# MD.net
KiCad netlist of a schematic drawn in EAGLE
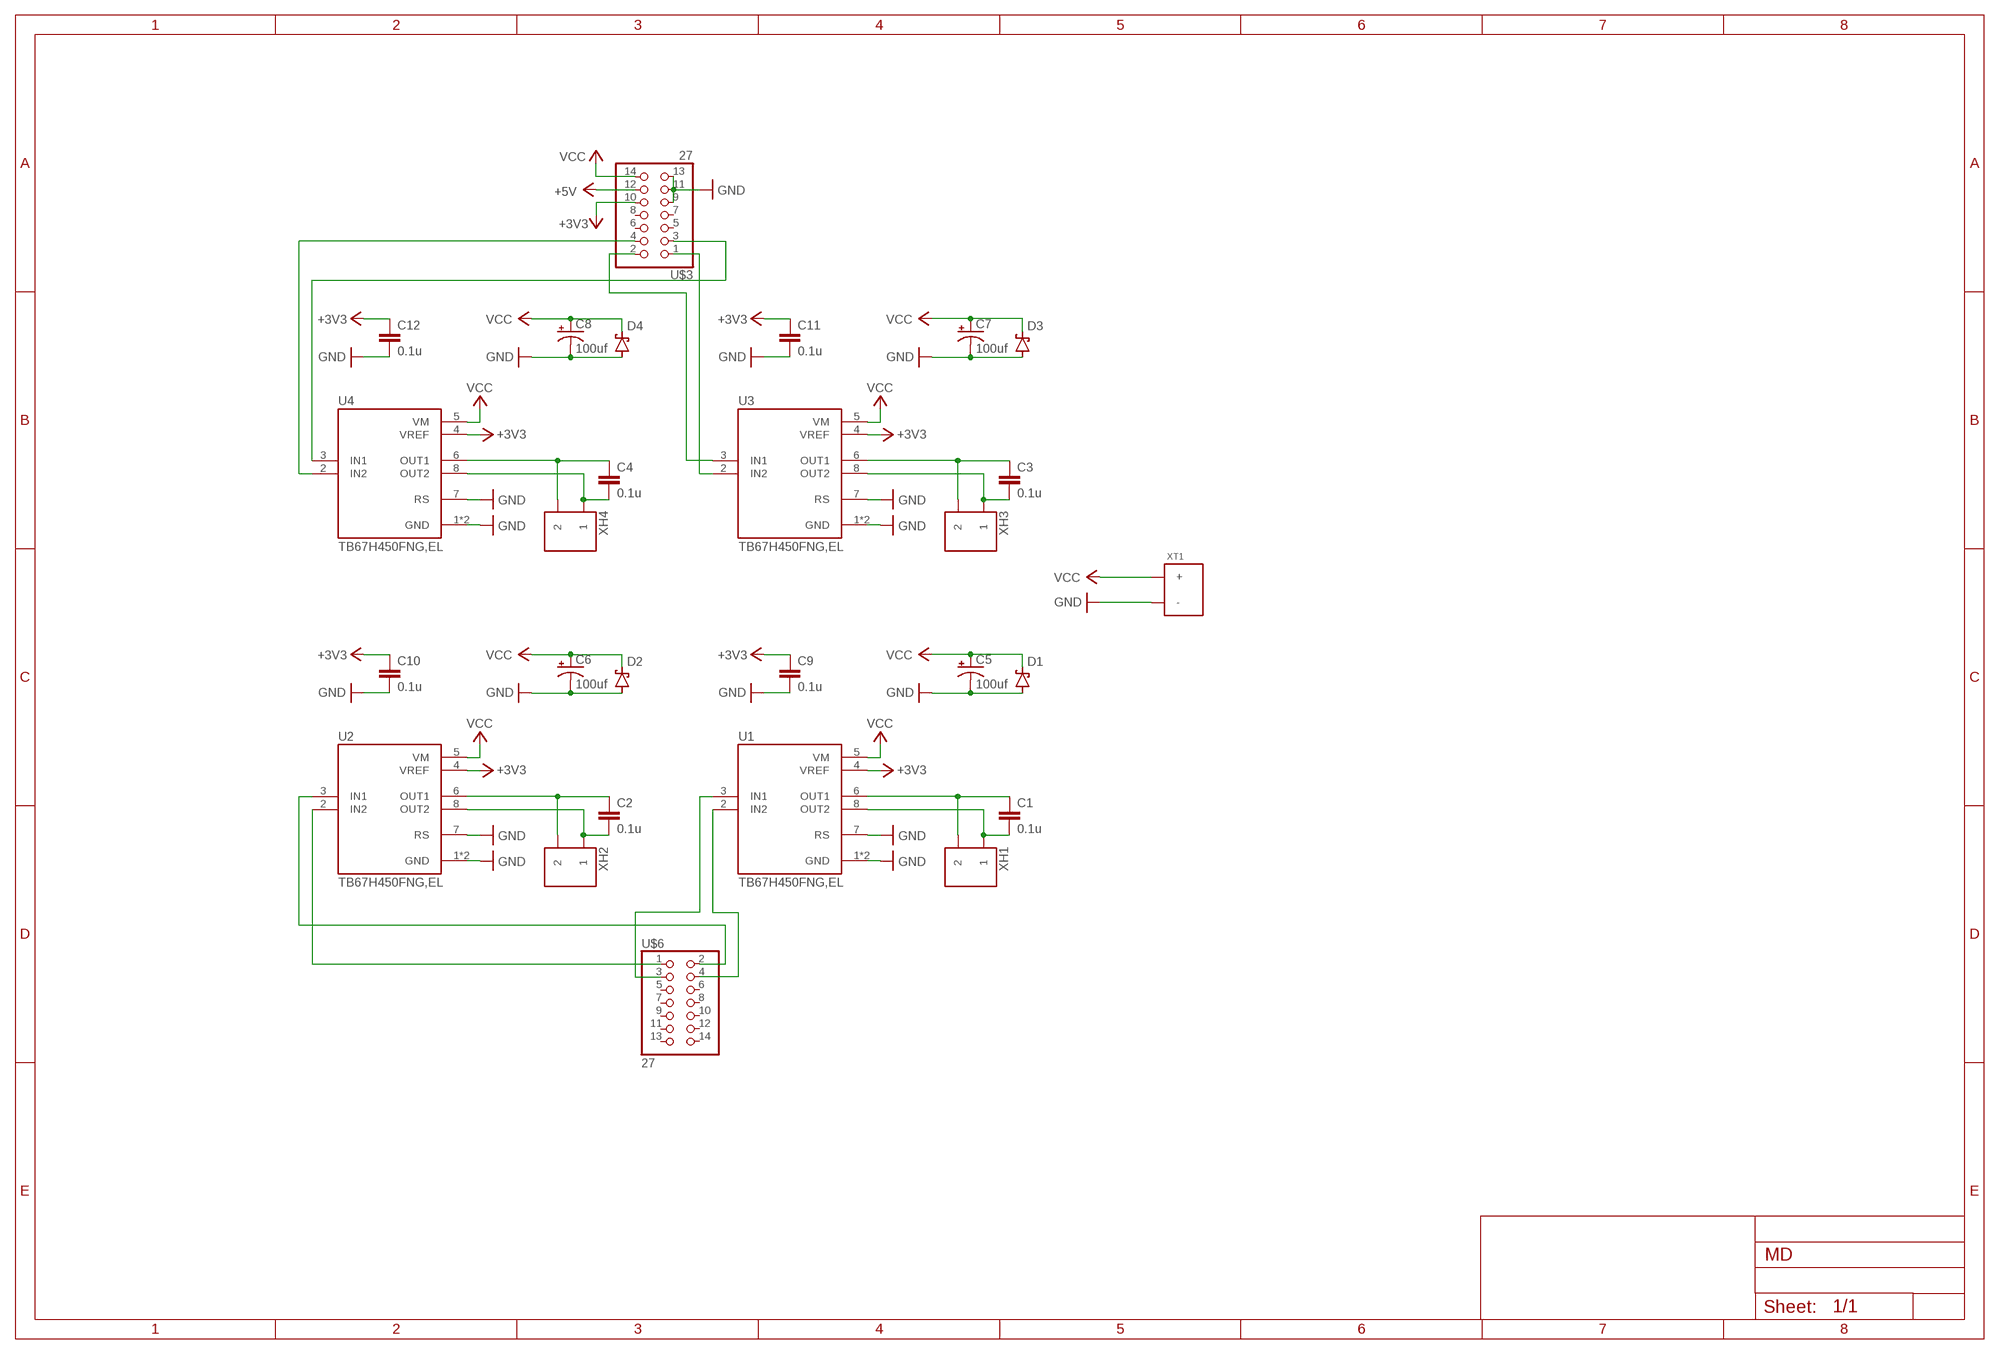
[diagram p0: schematic, sheet 1]

(export (version "E")
  (design (tool "Eeschema 10.0.6"))
  (components
    (comp (ref "C1")
      (value "0.1u")
      (footprint "eagle-import:C0603")
      (libsource (lib "eagle-import") (part "C-EUC0603"))
    )
    (comp (ref "C2")
      (value "0.1u")
      (footprint "eagle-import:C0603")
      (libsource (lib "eagle-import") (part "C-EUC0603"))
    )
    (comp (ref "C3")
      (value "0.1u")
      (footprint "eagle-import:C0603")
      (libsource (lib "eagle-import") (part "C-EUC0603"))
    )
    (comp (ref "C4")
      (value "0.1u")
      (footprint "eagle-import:C0603")
      (libsource (lib "eagle-import") (part "C-EUC0603"))
    )
    (comp (ref "C5")
      (value "100uf")
      (footprint "eagle-import:MH5")
      (libsource (lib "eagle-import") (part "MH5"))
    )
    (comp (ref "C6")
      (value "100uf")
      (footprint "eagle-import:MH5")
      (libsource (lib "eagle-import") (part "MH5"))
    )
    (comp (ref "C7")
      (value "100uf")
      (footprint "eagle-import:MH5")
      (libsource (lib "eagle-import") (part "MH5"))
    )
    (comp (ref "C8")
      (value "100uf")
      (footprint "eagle-import:MH5")
      (libsource (lib "eagle-import") (part "MH5"))
    )
    (comp (ref "C9")
      (value "0.1u")
      (footprint "eagle-import:C0603")
      (libsource (lib "eagle-import") (part "C-EUC0603"))
    )
    (comp (ref "C10")
      (value "0.1u")
      (footprint "eagle-import:C0603")
      (libsource (lib "eagle-import") (part "C-EUC0603"))
    )
    (comp (ref "C11")
      (value "0.1u")
      (footprint "eagle-import:C0603")
      (libsource (lib "eagle-import") (part "C-EUC0603"))
    )
    (comp (ref "C12")
      (value "0.1u")
      (footprint "eagle-import:C0603")
      (libsource (lib "eagle-import") (part "C-EUC0603"))
    )
    (comp (ref "D1")
      (value "SS2040FL")
      (footprint "eagle-import:SOD123FL")
      (libsource (lib "eagle-import") (part "SS2040FL"))
    )
    (comp (ref "D2")
      (value "SS2040FL")
      (footprint "eagle-import:SOD123FL")
      (libsource (lib "eagle-import") (part "SS2040FL"))
    )
    (comp (ref "D3")
      (value "SS2040FL")
      (footprint "eagle-import:SOD123FL")
      (libsource (lib "eagle-import") (part "SS2040FL"))
    )
    (comp (ref "D4")
      (value "SS2040FL")
      (footprint "eagle-import:SOD123FL")
      (libsource (lib "eagle-import") (part "SS2040FL"))
    )
    (comp (ref "U$3")
      (value "27")
      (footprint "eagle-import:2_7")
      (libsource (lib "eagle-import") (part "27"))
    )
    (comp (ref "U$6")
      (value "27")
      (footprint "eagle-import:2_7")
      (libsource (lib "eagle-import") (part "27"))
    )
    (comp (ref "U1")
      (value "TB67H450FNG,EL")
      (footprint "eagle-import:SOIC127P599X175-9N")
      (fields (field (name "MF") "Toshiba Semiconductor and Storage"))
      (libsource (lib "eagle-import") (part "TB67H450FNG,EL"))
    )
    (comp (ref "U2")
      (value "TB67H450FNG,EL")
      (footprint "eagle-import:SOIC127P599X175-9N")
      (fields (field (name "MF") "Toshiba Semiconductor and Storage"))
      (libsource (lib "eagle-import") (part "TB67H450FNG,EL"))
    )
    (comp (ref "U3")
      (value "TB67H450FNG,EL")
      (footprint "eagle-import:SOIC127P599X175-9N")
      (fields (field (name "MF") "Toshiba Semiconductor and Storage"))
      (libsource (lib "eagle-import") (part "TB67H450FNG,EL"))
    )
    (comp (ref "U4")
      (value "TB67H450FNG,EL")
      (footprint "eagle-import:SOIC127P599X175-9N")
      (fields (field (name "MF") "Toshiba Semiconductor and Storage"))
      (libsource (lib "eagle-import") (part "TB67H450FNG,EL"))
    )
    (comp (ref "XH1")
      (value "S2B")
      (footprint "eagle-import:S2B")
      (libsource (lib "eagle-import") (part "S2B"))
    )
    (comp (ref "XH2")
      (value "S2B")
      (footprint "eagle-import:S2B")
      (libsource (lib "eagle-import") (part "S2B"))
    )
    (comp (ref "XH3")
      (value "S2B")
      (footprint "eagle-import:S2B")
      (libsource (lib "eagle-import") (part "S2B"))
    )
    (comp (ref "XH4")
      (value "S2B")
      (footprint "eagle-import:S2B")
      (libsource (lib "eagle-import") (part "S2B"))
    )
    (comp (ref "XT1")
      (value "XT30PW-M")
      (footprint "eagle-import:XT30PW-M")
      (libsource (lib "eagle-import") (part "XT30PW-M"))
    )
  )
  (nets
    (net (code "1") (name "+3V3") (class "Default")
      (node (ref "C10") (pin "1") (pinfunction "1_1") (pintype "passive"))
      (node (ref "C11") (pin "1") (pinfunction "1_1") (pintype "passive"))
      (node (ref "C12") (pin "1") (pinfunction "1_1") (pintype "passive"))
      (node (ref "C9") (pin "1") (pinfunction "1_1") (pintype "passive"))
      (node (ref "U$3") (pin "10") (pinfunction "10_10") (pintype "passive"))
      (node (ref "U1") (pin "4") (pinfunction "VREF_4") (pintype "power_in"))
      (node (ref "U2") (pin "4") (pinfunction "VREF_4") (pintype "power_in"))
      (node (ref "U3") (pin "4") (pinfunction "VREF_4") (pintype "power_in"))
      (node (ref "U4") (pin "4") (pinfunction "VREF_4") (pintype "power_in"))
    )
    (net (code "2") (name "+5V") (class "Default")
      (node (ref "U$3") (pin "12") (pinfunction "12_12") (pintype "passive"))
    )
    (net (code "3") (name "GND") (class "Default")
      (node (ref "C10") (pin "2") (pinfunction "2_2") (pintype "passive"))
      (node (ref "C11") (pin "2") (pinfunction "2_2") (pintype "passive"))
      (node (ref "C12") (pin "2") (pinfunction "2_2") (pintype "passive"))
      (node (ref "C5") (pin "-") (pinfunction "-_-") (pintype "passive"))
      (node (ref "C6") (pin "-") (pinfunction "-_-") (pintype "passive"))
      (node (ref "C7") (pin "-") (pinfunction "-_-") (pintype "passive"))
      (node (ref "C8") (pin "-") (pinfunction "-_-") (pintype "passive"))
      (node (ref "C9") (pin "2") (pinfunction "2_2") (pintype "passive"))
      (node (ref "D1") (pin "A") (pinfunction "A_A") (pintype "passive"))
      (node (ref "D2") (pin "A") (pinfunction "A_A") (pintype "passive"))
      (node (ref "D3") (pin "A") (pinfunction "A_A") (pintype "passive"))
      (node (ref "D4") (pin "A") (pinfunction "A_A") (pintype "passive"))
      (node (ref "U$3") (pin "11") (pinfunction "11_11") (pintype "passive"))
      (node (ref "U$3") (pin "13") (pinfunction "13_13") (pintype "passive"))
      (node (ref "U$3") (pin "9") (pinfunction "9_9") (pintype "passive"))
      (node (ref "U1") (pin "1") (pinfunction "GND_1") (pintype "power_in"))
      (node (ref "U1") (pin "7") (pinfunction "RS_7") (pintype "output"))
      (node (ref "U1") (pin "9") (pinfunction "GND_9") (pintype "power_in"))
      (node (ref "U2") (pin "1") (pinfunction "GND_1") (pintype "power_in"))
      (node (ref "U2") (pin "7") (pinfunction "RS_7") (pintype "output"))
      (node (ref "U2") (pin "9") (pinfunction "GND_9") (pintype "power_in"))
      (node (ref "U3") (pin "1") (pinfunction "GND_1") (pintype "power_in"))
      (node (ref "U3") (pin "7") (pinfunction "RS_7") (pintype "output"))
      (node (ref "U3") (pin "9") (pinfunction "GND_9") (pintype "power_in"))
      (node (ref "U4") (pin "1") (pinfunction "GND_1") (pintype "power_in"))
      (node (ref "U4") (pin "7") (pinfunction "RS_7") (pintype "output"))
      (node (ref "U4") (pin "9") (pinfunction "GND_9") (pintype "power_in"))
      (node (ref "XT1") (pin "-") (pinfunction "-_-") (pintype "bidirectional"))
    )
    (net (code "4") (name "Net-(U1-IN1)") (class "Default")
      (node (ref "U$6") (pin "3") (pinfunction "3_3") (pintype "passive"))
      (node (ref "U1") (pin "3") (pinfunction "IN1_3") (pintype "input"))
    )
    (net (code "5") (name "Net-(U1-IN2)") (class "Default")
      (node (ref "U$6") (pin "4") (pinfunction "4_4") (pintype "passive"))
      (node (ref "U1") (pin "2") (pinfunction "IN2_2") (pintype "input"))
    )
    (net (code "6") (name "Net-(U1-OUT1)") (class "Default")
      (node (ref "C1") (pin "1") (pinfunction "1_1") (pintype "passive"))
      (node (ref "U1") (pin "6") (pinfunction "OUT1_6") (pintype "output"))
      (node (ref "XH1") (pin "2") (pinfunction "2_2") (pintype "bidirectional"))
    )
    (net (code "7") (name "Net-(U1-OUT2)") (class "Default")
      (node (ref "C1") (pin "2") (pinfunction "2_2") (pintype "passive"))
      (node (ref "U1") (pin "8") (pinfunction "OUT2_8") (pintype "output"))
      (node (ref "XH1") (pin "1") (pinfunction "1_1") (pintype "bidirectional"))
    )
    (net (code "8") (name "Net-(U2-IN1)") (class "Default")
      (node (ref "U$6") (pin "2") (pinfunction "2_2") (pintype "passive"))
      (node (ref "U2") (pin "3") (pinfunction "IN1_3") (pintype "input"))
    )
    (net (code "9") (name "Net-(U2-IN2)") (class "Default")
      (node (ref "U$6") (pin "1") (pinfunction "1_1") (pintype "passive"))
      (node (ref "U2") (pin "2") (pinfunction "IN2_2") (pintype "input"))
    )
    (net (code "10") (name "Net-(U2-OUT1)") (class "Default")
      (node (ref "C2") (pin "1") (pinfunction "1_1") (pintype "passive"))
      (node (ref "U2") (pin "6") (pinfunction "OUT1_6") (pintype "output"))
      (node (ref "XH2") (pin "2") (pinfunction "2_2") (pintype "bidirectional"))
    )
    (net (code "11") (name "Net-(U2-OUT2)") (class "Default")
      (node (ref "C2") (pin "2") (pinfunction "2_2") (pintype "passive"))
      (node (ref "U2") (pin "8") (pinfunction "OUT2_8") (pintype "output"))
      (node (ref "XH2") (pin "1") (pinfunction "1_1") (pintype "bidirectional"))
    )
    (net (code "12") (name "Net-(U3-IN1)") (class "Default")
      (node (ref "U$3") (pin "2") (pinfunction "2_2") (pintype "passive"))
      (node (ref "U3") (pin "3") (pinfunction "IN1_3") (pintype "input"))
    )
    (net (code "13") (name "Net-(U3-IN2)") (class "Default")
      (node (ref "U$3") (pin "1") (pinfunction "1_1") (pintype "passive"))
      (node (ref "U3") (pin "2") (pinfunction "IN2_2") (pintype "input"))
    )
    (net (code "14") (name "Net-(U3-OUT1)") (class "Default")
      (node (ref "C3") (pin "1") (pinfunction "1_1") (pintype "passive"))
      (node (ref "U3") (pin "6") (pinfunction "OUT1_6") (pintype "output"))
      (node (ref "XH3") (pin "2") (pinfunction "2_2") (pintype "bidirectional"))
    )
    (net (code "15") (name "Net-(U3-OUT2)") (class "Default")
      (node (ref "C3") (pin "2") (pinfunction "2_2") (pintype "passive"))
      (node (ref "U3") (pin "8") (pinfunction "OUT2_8") (pintype "output"))
      (node (ref "XH3") (pin "1") (pinfunction "1_1") (pintype "bidirectional"))
    )
    (net (code "16") (name "Net-(U4-IN1)") (class "Default")
      (node (ref "U$3") (pin "3") (pinfunction "3_3") (pintype "passive"))
      (node (ref "U4") (pin "3") (pinfunction "IN1_3") (pintype "input"))
    )
    (net (code "17") (name "Net-(U4-IN2)") (class "Default")
      (node (ref "U$3") (pin "4") (pinfunction "4_4") (pintype "passive"))
      (node (ref "U4") (pin "2") (pinfunction "IN2_2") (pintype "input"))
    )
    (net (code "18") (name "Net-(U4-OUT1)") (class "Default")
      (node (ref "C4") (pin "1") (pinfunction "1_1") (pintype "passive"))
      (node (ref "U4") (pin "6") (pinfunction "OUT1_6") (pintype "output"))
      (node (ref "XH4") (pin "2") (pinfunction "2_2") (pintype "bidirectional"))
    )
    (net (code "19") (name "Net-(U4-OUT2)") (class "Default")
      (node (ref "C4") (pin "2") (pinfunction "2_2") (pintype "passive"))
      (node (ref "U4") (pin "8") (pinfunction "OUT2_8") (pintype "output"))
      (node (ref "XH4") (pin "1") (pinfunction "1_1") (pintype "bidirectional"))
    )
    (net (code "20") (name "VCC") (class "Default")
      (node (ref "C5") (pin "+") (pinfunction "+_+") (pintype "passive"))
      (node (ref "C6") (pin "+") (pinfunction "+_+") (pintype "passive"))
      (node (ref "C7") (pin "+") (pinfunction "+_+") (pintype "passive"))
      (node (ref "C8") (pin "+") (pinfunction "+_+") (pintype "passive"))
      (node (ref "D1") (pin "C") (pinfunction "C_C") (pintype "passive"))
      (node (ref "D2") (pin "C") (pinfunction "C_C") (pintype "passive"))
      (node (ref "D3") (pin "C") (pinfunction "C_C") (pintype "passive"))
      (node (ref "D4") (pin "C") (pinfunction "C_C") (pintype "passive"))
      (node (ref "U$3") (pin "14") (pinfunction "14_14") (pintype "passive"))
      (node (ref "U1") (pin "5") (pinfunction "VM_5") (pintype "power_in"))
      (node (ref "U2") (pin "5") (pinfunction "VM_5") (pintype "power_in"))
      (node (ref "U3") (pin "5") (pinfunction "VM_5") (pintype "power_in"))
      (node (ref "U4") (pin "5") (pinfunction "VM_5") (pintype "power_in"))
      (node (ref "XT1") (pin "+") (pinfunction "+_+") (pintype "bidirectional"))
    )
    (net (code "21") (name "unconnected-(U$3-Pad5)") (class "Default")
      (node (ref "U$3") (pin "5") (pinfunction "5_5") (pintype "passive"))
    )
    (net (code "22") (name "unconnected-(U$3-Pad6)") (class "Default")
      (node (ref "U$3") (pin "6") (pinfunction "6_6") (pintype "passive"))
    )
    (net (code "23") (name "unconnected-(U$3-Pad7)") (class "Default")
      (node (ref "U$3") (pin "7") (pinfunction "7_7") (pintype "passive"))
    )
    (net (code "24") (name "unconnected-(U$3-Pad8)") (class "Default")
      (node (ref "U$3") (pin "8") (pinfunction "8_8") (pintype "passive"))
    )
    (net (code "25") (name "unconnected-(U$6-Pad5)") (class "Default")
      (node (ref "U$6") (pin "5") (pinfunction "5_5") (pintype "passive"))
    )
    (net (code "26") (name "unconnected-(U$6-Pad6)") (class "Default")
      (node (ref "U$6") (pin "6") (pinfunction "6_6") (pintype "passive"))
    )
    (net (code "27") (name "unconnected-(U$6-Pad7)") (class "Default")
      (node (ref "U$6") (pin "7") (pinfunction "7_7") (pintype "passive"))
    )
    (net (code "28") (name "unconnected-(U$6-Pad8)") (class "Default")
      (node (ref "U$6") (pin "8") (pinfunction "8_8") (pintype "passive"))
    )
    (net (code "29") (name "unconnected-(U$6-Pad9)") (class "Default")
      (node (ref "U$6") (pin "9") (pinfunction "9_9") (pintype "passive"))
    )
    (net (code "30") (name "unconnected-(U$6-Pad10)") (class "Default")
      (node (ref "U$6") (pin "10") (pinfunction "10_10") (pintype "passive"))
    )
    (net (code "31") (name "unconnected-(U$6-Pad11)") (class "Default")
      (node (ref "U$6") (pin "11") (pinfunction "11_11") (pintype "passive"))
    )
    (net (code "32") (name "unconnected-(U$6-Pad12)") (class "Default")
      (node (ref "U$6") (pin "12") (pinfunction "12_12") (pintype "passive"))
    )
    (net (code "33") (name "unconnected-(U$6-Pad13)") (class "Default")
      (node (ref "U$6") (pin "13") (pinfunction "13_13") (pintype "passive"))
    )
    (net (code "34") (name "unconnected-(U$6-Pad14)") (class "Default")
      (node (ref "U$6") (pin "14") (pinfunction "14_14") (pintype "passive"))
    )
  )
)
